# Sensor_adelante.net
KiCad netlist of a schematic drawn in EAGLE
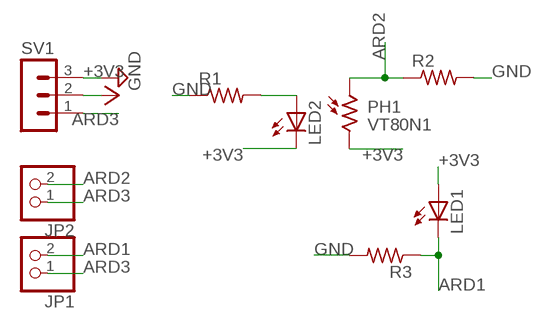
[diagram p0: schematic, sheet 1]

(export (version "E")
  (design (tool "Eeschema 10.0.6"))
  (components
    (comp (ref "JP1")
      (value "PINHD-1X2")
      (footprint "eagle-import:1X02")
      (libsource (lib "eagle-import") (part "PINHD-1X2"))
    )
    (comp (ref "JP2")
      (value "PINHD-1X2")
      (footprint "eagle-import:1X02")
      (libsource (lib "eagle-import") (part "PINHD-1X2"))
    )
    (comp (ref "LED1")
      (value "LED5MM")
      (footprint "eagle-import:LED5MM")
      (libsource (lib "eagle-import") (part "LED5MM"))
    )
    (comp (ref "LED2")
      (value "LED5MM")
      (footprint "eagle-import:LED5MM")
      (libsource (lib "eagle-import") (part "LED5MM"))
    )
    (comp (ref "PH1")
      (value "VT80N1")
      (footprint "eagle-import:VT800")
      (libsource (lib "eagle-import") (part "VT80N1"))
    )
    (comp (ref "R1")
      (value "R-US_0207/15")
      (footprint "eagle-import:0207_15")
      (libsource (lib "eagle-import") (part "R-US_0207/15"))
    )
    (comp (ref "R2")
      (value "R-US_0207/15")
      (footprint "eagle-import:0207_15")
      (libsource (lib "eagle-import") (part "R-US_0207/15"))
    )
    (comp (ref "R3")
      (value "R-US_0207/15")
      (footprint "eagle-import:0207_15")
      (libsource (lib "eagle-import") (part "R-US_0207/15"))
    )
    (comp (ref "SV1")
      (value "MA03-1")
      (footprint "eagle-import:MA03-1")
      (libsource (lib "eagle-import") (part "MA03-1"))
    )
  )
  (nets
    (net (code "1") (name "+3V3") (class "Default")
      (node (ref "LED1") (pin "A") (pinfunction "A_A") (pintype "passive"))
      (node (ref "LED2") (pin "K") (pinfunction "C_K") (pintype "passive"))
      (node (ref "PH1") (pin "2") (pinfunction "2_2") (pintype "passive"))
      (node (ref "SV1") (pin "2") (pinfunction "2_2") (pintype "passive"))
    )
    (net (code "2") (name "/ARD1") (class "Default")
      (node (ref "JP1") (pin "2") (pinfunction "2_2") (pintype "passive"))
      (node (ref "LED1") (pin "K") (pinfunction "C_K") (pintype "passive"))
      (node (ref "R3") (pin "1") (pinfunction "1_1") (pintype "passive"))
    )
    (net (code "3") (name "/ARD2") (class "Default")
      (node (ref "JP2") (pin "2") (pinfunction "2_2") (pintype "passive"))
      (node (ref "PH1") (pin "1") (pinfunction "1_1") (pintype "passive"))
      (node (ref "R2") (pin "1") (pinfunction "1_1") (pintype "passive"))
    )
    (net (code "4") (name "/ARD3") (class "Default")
      (node (ref "JP1") (pin "1") (pinfunction "1_1") (pintype "passive"))
      (node (ref "JP2") (pin "1") (pinfunction "1_1") (pintype "passive"))
      (node (ref "SV1") (pin "1") (pinfunction "1_1") (pintype "passive"))
    )
    (net (code "5") (name "GND") (class "Default")
      (node (ref "R1") (pin "1") (pinfunction "1_1") (pintype "passive"))
      (node (ref "R2") (pin "2") (pinfunction "2_2") (pintype "passive"))
      (node (ref "R3") (pin "2") (pinfunction "2_2") (pintype "passive"))
      (node (ref "SV1") (pin "3") (pinfunction "3_3") (pintype "passive"))
    )
    (net (code "6") (name "Net-(LED2-PadA)") (class "Default")
      (node (ref "LED2") (pin "A") (pinfunction "A_A") (pintype "passive"))
      (node (ref "R1") (pin "2") (pinfunction "2_2") (pintype "passive"))
    )
  )
)
